# 16-PPSMUX_DPLLSMAMUX.net
KiCad netlist of a schematic drawn in Altium Designer
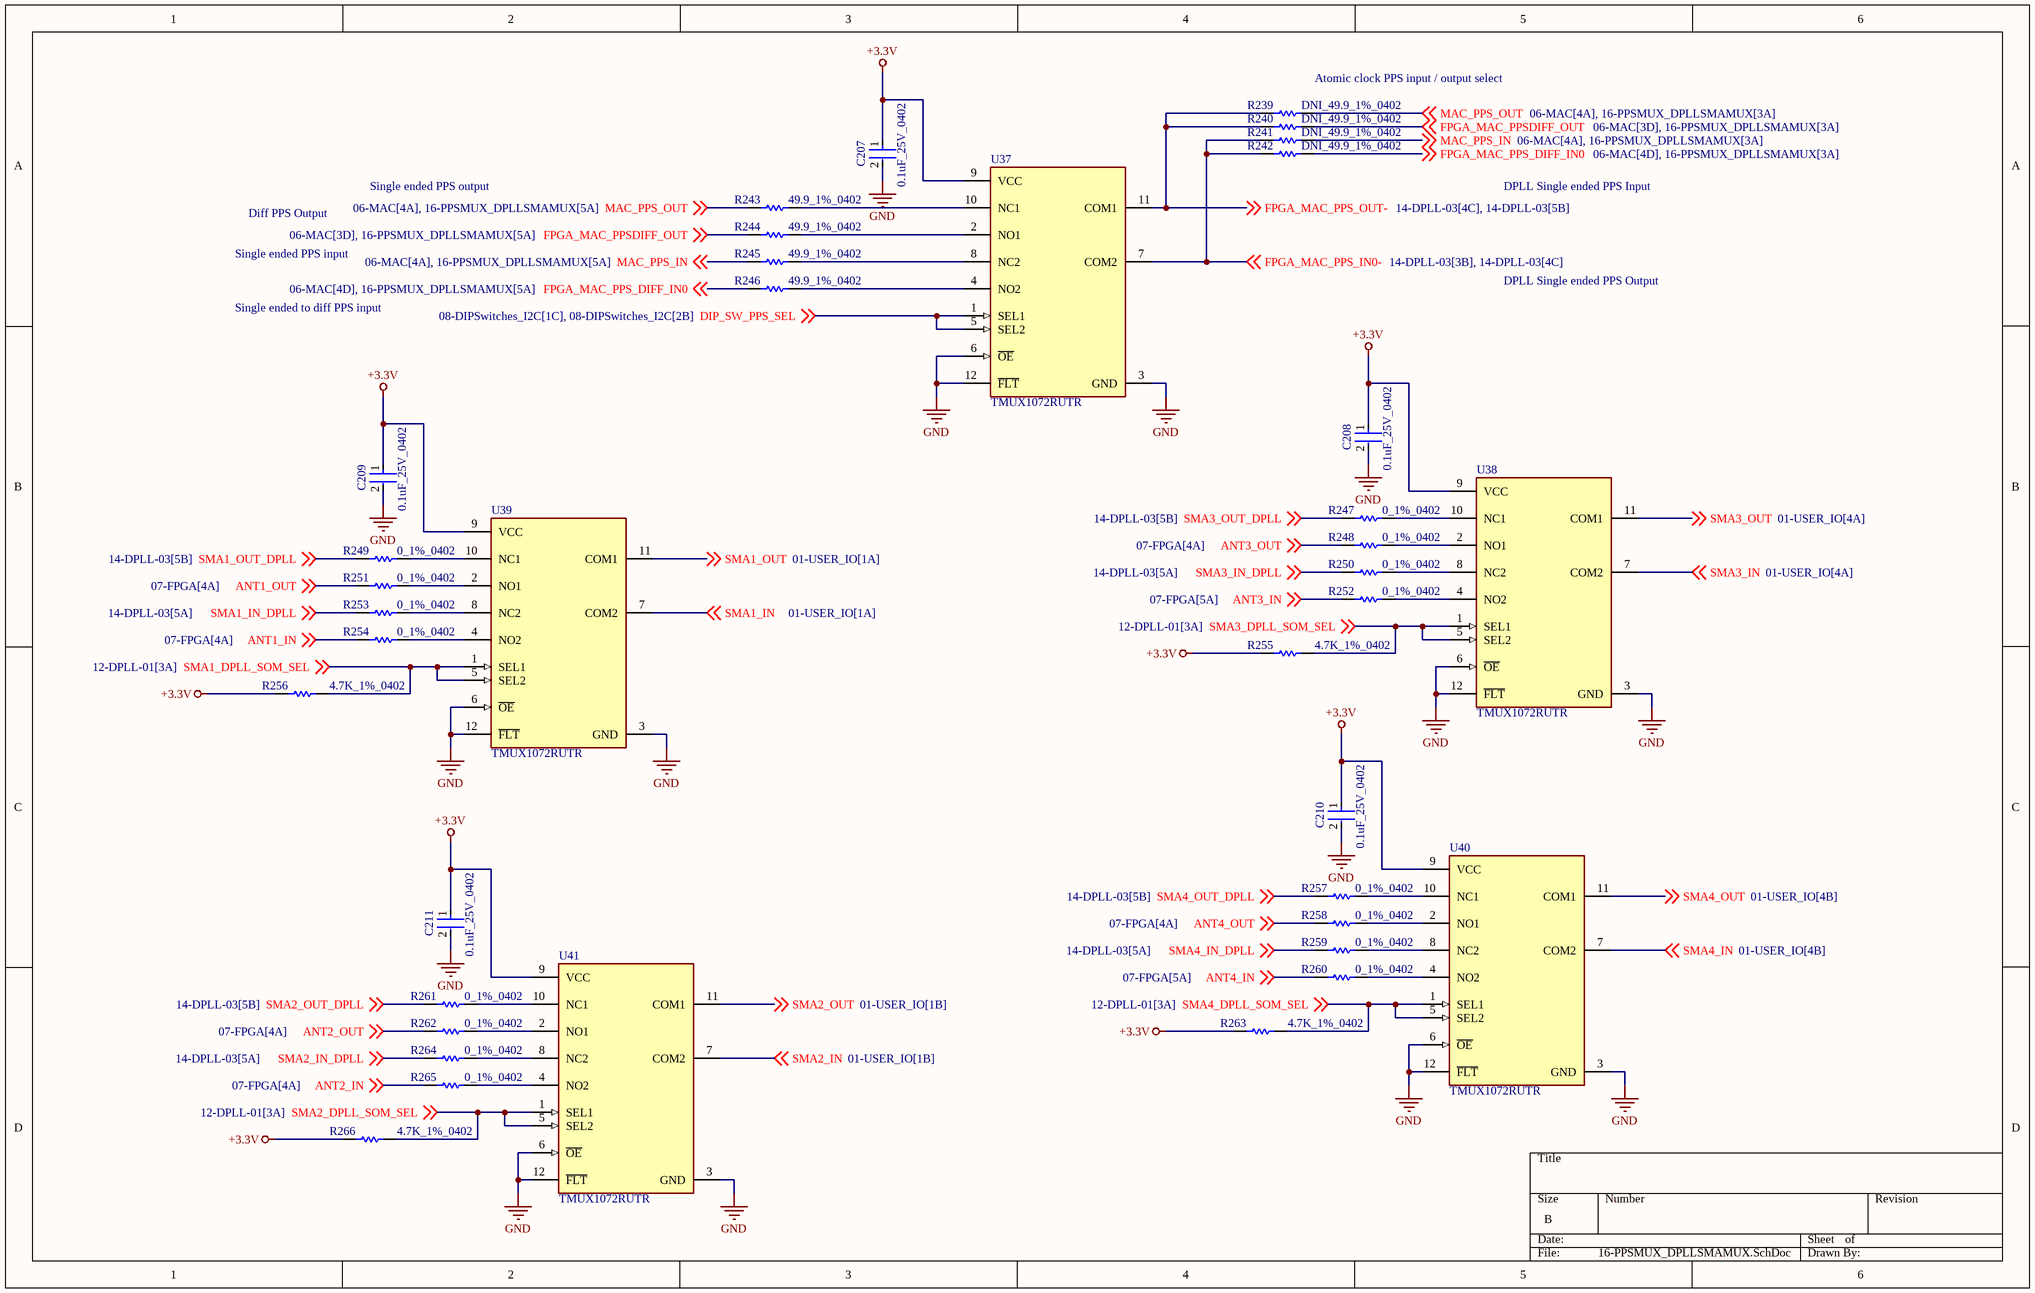
[diagram p0: 16-PPSMUX_DPLLSMAMUX.SchDoc]

(export (version "E")
  (design (tool "Eeschema 10.0.6"))
  (components
    (comp (ref "C207")
      (value "0.1uF_25V_0402")
      (footprint "FP-0402-L_1_0_1-W_0_5_0_1-IPC_C")
      (description "General Purpose Ceramic Capacitor, 0402, 100nF, 10%, X7R, 15%, 25V")
      (fields (field (name "VOLTAGE") "25V") (field (name "TOLERANCE") "10%"))
      (libsource (lib "Altium Content Vault") (part "b4654b650e69147ec39a6b967a45e02"))
    )
    (comp (ref "C208")
      (value "0.1uF_25V_0402")
      (footprint "FP-0402-L_1_0_1-W_0_5_0_1-IPC_C")
      (description "General Purpose Ceramic Capacitor, 0402, 100nF, 10%, X7R, 15%, 25V")
      (fields (field (name "VOLTAGE") "25V") (field (name "TOLERANCE") "10%"))
      (libsource (lib "Altium Content Vault") (part "b4654b650e69147ec39a6b967a45e02"))
    )
    (comp (ref "C209")
      (value "0.1uF_25V_0402")
      (footprint "FP-0402-L_1_0_1-W_0_5_0_1-IPC_C")
      (description "General Purpose Ceramic Capacitor, 0402, 100nF, 10%, X7R, 15%, 25V")
      (fields (field (name "VOLTAGE") "25V") (field (name "TOLERANCE") "10%"))
      (libsource (lib "Altium Content Vault") (part "b4654b650e69147ec39a6b967a45e02"))
    )
    (comp (ref "C210")
      (value "0.1uF_25V_0402")
      (footprint "FP-0402-L_1_0_1-W_0_5_0_1-IPC_C")
      (description "General Purpose Ceramic Capacitor, 0402, 100nF, 10%, X7R, 15%, 25V")
      (fields (field (name "VOLTAGE") "25V") (field (name "TOLERANCE") "10%"))
      (libsource (lib "Altium Content Vault") (part "b4654b650e69147ec39a6b967a45e02"))
    )
    (comp (ref "C211")
      (value "0.1uF_25V_0402")
      (footprint "FP-0402-L_1_0_1-W_0_5_0_1-IPC_C")
      (description "General Purpose Ceramic Capacitor, 0402, 100nF, 10%, X7R, 15%, 25V")
      (fields (field (name "VOLTAGE") "25V") (field (name "TOLERANCE") "10%"))
      (libsource (lib "Altium Content Vault") (part "b4654b650e69147ec39a6b967a45e02"))
    )
    (comp (ref "R239")
      (value "DNI_49.9_1%_0402")
      (footprint "RESC1005X40X25LL05T10")
      (fields (field (name "MANUFACTURER") "Yageo / Phycomp") (field (name "PART NUMBER") "RC0402FR-0749R9L"))
      (libsource (lib "Altium Content Vault") (part "RES"))
    )
    (comp (ref "R240")
      (value "DNI_49.9_1%_0402")
      (footprint "RESC1005X40X25LL05T10")
      (fields (field (name "MANUFACTURER") "Yageo / Phycomp") (field (name "PART NUMBER") "RC0402FR-0749R9L"))
      (libsource (lib "Altium Content Vault") (part "RES"))
    )
    (comp (ref "R241")
      (value "DNI_49.9_1%_0402")
      (footprint "RESC1005X40X25LL05T10")
      (fields (field (name "MANUFACTURER") "Yageo / Phycomp") (field (name "PART NUMBER") "RC0402FR-0749R9L"))
      (libsource (lib "Altium Content Vault") (part "RES"))
    )
    (comp (ref "R242")
      (value "DNI_49.9_1%_0402")
      (footprint "RESC1005X40X25LL05T10")
      (fields (field (name "MANUFACTURER") "Yageo / Phycomp") (field (name "PART NUMBER") "RC0402FR-0749R9L"))
      (libsource (lib "Altium Content Vault") (part "RES"))
    )
    (comp (ref "R243")
      (value "49.9_1%_0402")
      (footprint "RESC1005X40X25LL05T10")
      (fields (field (name "MANUFACTURER") "Yageo / Phycomp") (field (name "PART NUMBER") "RC0402FR-0749R9L"))
      (libsource (lib "Altium Content Vault") (part "RES"))
    )
    (comp (ref "R244")
      (value "49.9_1%_0402")
      (footprint "RESC1005X40X25LL05T10")
      (fields (field (name "MANUFACTURER") "Yageo / Phycomp") (field (name "PART NUMBER") "RC0402FR-0749R9L"))
      (libsource (lib "Altium Content Vault") (part "RES"))
    )
    (comp (ref "R245")
      (value "49.9_1%_0402")
      (footprint "RESC1005X40X25LL05T10")
      (fields (field (name "MANUFACTURER") "Yageo / Phycomp") (field (name "PART NUMBER") "RC0402FR-0749R9L"))
      (libsource (lib "Altium Content Vault") (part "RES"))
    )
    (comp (ref "R246")
      (value "49.9_1%_0402")
      (footprint "RESC1005X40X25LL05T10")
      (fields (field (name "MANUFACTURER") "Yageo / Phycomp") (field (name "PART NUMBER") "RC0402FR-0749R9L"))
      (libsource (lib "Altium Content Vault") (part "RES"))
    )
    (comp (ref "R247")
      (value "0_1%_0402")
      (footprint "RESC1005X40X25LL05T05")
      (description "Chip Resistor, 0 Ohm, 0.1 W, -55 to 155 degC, 0402 (1005 Metric), RoHS, Tape and Reel")
      (fields (field (name "MANUFACTURER") "Panasonic") (field (name "TOLERANCE") "5%"))
      (libsource (lib "Altium Content Vault") (part "RES-2"))
    )
    (comp (ref "R248")
      (value "0_1%_0402")
      (footprint "RESC1005X40X25LL05T05")
      (description "Chip Resistor, 0 Ohm, 0.1 W, -55 to 155 degC, 0402 (1005 Metric), RoHS, Tape and Reel")
      (fields (field (name "MANUFACTURER") "Panasonic") (field (name "TOLERANCE") "5%"))
      (libsource (lib "Altium Content Vault") (part "RES-2"))
    )
    (comp (ref "R249")
      (value "0_1%_0402")
      (footprint "RESC1005X40X25LL05T05")
      (description "Chip Resistor, 0 Ohm, 0.1 W, -55 to 155 degC, 0402 (1005 Metric), RoHS, Tape and Reel")
      (fields (field (name "MANUFACTURER") "Panasonic") (field (name "TOLERANCE") "5%"))
      (libsource (lib "Altium Content Vault") (part "RES-2"))
    )
    (comp (ref "R250")
      (value "0_1%_0402")
      (footprint "RESC1005X40X25LL05T05")
      (description "Chip Resistor, 0 Ohm, 0.1 W, -55 to 155 degC, 0402 (1005 Metric), RoHS, Tape and Reel")
      (fields (field (name "MANUFACTURER") "Panasonic") (field (name "TOLERANCE") "5%"))
      (libsource (lib "Altium Content Vault") (part "RES-2"))
    )
    (comp (ref "R251")
      (value "0_1%_0402")
      (footprint "RESC1005X40X25LL05T05")
      (description "Chip Resistor, 0 Ohm, 0.1 W, -55 to 155 degC, 0402 (1005 Metric), RoHS, Tape and Reel")
      (fields (field (name "MANUFACTURER") "Panasonic") (field (name "TOLERANCE") "5%"))
      (libsource (lib "Altium Content Vault") (part "RES-2"))
    )
    (comp (ref "R252")
      (value "0_1%_0402")
      (footprint "RESC1005X40X25LL05T05")
      (description "Chip Resistor, 0 Ohm, 0.1 W, -55 to 155 degC, 0402 (1005 Metric), RoHS, Tape and Reel")
      (fields (field (name "MANUFACTURER") "Panasonic") (field (name "TOLERANCE") "5%"))
      (libsource (lib "Altium Content Vault") (part "RES-2"))
    )
    (comp (ref "R253")
      (value "0_1%_0402")
      (footprint "RESC1005X40X25LL05T05")
      (description "Chip Resistor, 0 Ohm, 0.1 W, -55 to 155 degC, 0402 (1005 Metric), RoHS, Tape and Reel")
      (fields (field (name "MANUFACTURER") "Panasonic") (field (name "TOLERANCE") "5%"))
      (libsource (lib "Altium Content Vault") (part "RES-2"))
    )
    (comp (ref "R254")
      (value "0_1%_0402")
      (footprint "RESC1005X40X25LL05T05")
      (description "Chip Resistor, 0 Ohm, 0.1 W, -55 to 155 degC, 0402 (1005 Metric), RoHS, Tape and Reel")
      (fields (field (name "MANUFACTURER") "Panasonic") (field (name "TOLERANCE") "5%"))
      (libsource (lib "Altium Content Vault") (part "RES-2"))
    )
    (comp (ref "R255")
      (value "4.7K_1%_0402")
      (footprint "RESC1005X40X25NL10T10")
      (fields (field (name "MANUFACTURER") "Bourns") (field (name "PART NUMBER") "CR0402-FX-4701GLF"))
      (libsource (lib "Altium Content Vault") (part "RES"))
    )
    (comp (ref "R256")
      (value "4.7K_1%_0402")
      (footprint "RESC1005X40X25NL10T10")
      (fields (field (name "MANUFACTURER") "Bourns") (field (name "PART NUMBER") "CR0402-FX-4701GLF"))
      (libsource (lib "Altium Content Vault") (part "RES"))
    )
    (comp (ref "R257")
      (value "0_1%_0402")
      (footprint "RESC1005X40X25LL05T05")
      (description "Chip Resistor, 0 Ohm, 0.1 W, -55 to 155 degC, 0402 (1005 Metric), RoHS, Tape and Reel")
      (fields (field (name "MANUFACTURER") "Panasonic") (field (name "TOLERANCE") "5%"))
      (libsource (lib "Altium Content Vault") (part "RES-2"))
    )
    (comp (ref "R258")
      (value "0_1%_0402")
      (footprint "RESC1005X40X25LL05T05")
      (description "Chip Resistor, 0 Ohm, 0.1 W, -55 to 155 degC, 0402 (1005 Metric), RoHS, Tape and Reel")
      (fields (field (name "MANUFACTURER") "Panasonic") (field (name "TOLERANCE") "5%"))
      (libsource (lib "Altium Content Vault") (part "RES-2"))
    )
    (comp (ref "R259")
      (value "0_1%_0402")
      (footprint "RESC1005X40X25LL05T05")
      (description "Chip Resistor, 0 Ohm, 0.1 W, -55 to 155 degC, 0402 (1005 Metric), RoHS, Tape and Reel")
      (fields (field (name "MANUFACTURER") "Panasonic") (field (name "TOLERANCE") "5%"))
      (libsource (lib "Altium Content Vault") (part "RES-2"))
    )
    (comp (ref "R260")
      (value "0_1%_0402")
      (footprint "RESC1005X40X25LL05T05")
      (description "Chip Resistor, 0 Ohm, 0.1 W, -55 to 155 degC, 0402 (1005 Metric), RoHS, Tape and Reel")
      (fields (field (name "MANUFACTURER") "Panasonic") (field (name "TOLERANCE") "5%"))
      (libsource (lib "Altium Content Vault") (part "RES-2"))
    )
    (comp (ref "R261")
      (value "0_1%_0402")
      (footprint "RESC1005X40X25LL05T05")
      (description "Chip Resistor, 0 Ohm, 0.1 W, -55 to 155 degC, 0402 (1005 Metric), RoHS, Tape and Reel")
      (fields (field (name "MANUFACTURER") "Panasonic") (field (name "TOLERANCE") "5%"))
      (libsource (lib "Altium Content Vault") (part "RES-2"))
    )
    (comp (ref "R262")
      (value "0_1%_0402")
      (footprint "RESC1005X40X25LL05T05")
      (description "Chip Resistor, 0 Ohm, 0.1 W, -55 to 155 degC, 0402 (1005 Metric), RoHS, Tape and Reel")
      (fields (field (name "MANUFACTURER") "Panasonic") (field (name "TOLERANCE") "5%"))
      (libsource (lib "Altium Content Vault") (part "RES-2"))
    )
    (comp (ref "R263")
      (value "4.7K_1%_0402")
      (footprint "RESC1005X40X25NL10T10")
      (fields (field (name "MANUFACTURER") "Bourns") (field (name "PART NUMBER") "CR0402-FX-4701GLF"))
      (libsource (lib "Altium Content Vault") (part "RES"))
    )
    (comp (ref "R264")
      (value "0_1%_0402")
      (footprint "RESC1005X40X25LL05T05")
      (description "Chip Resistor, 0 Ohm, 0.1 W, -55 to 155 degC, 0402 (1005 Metric), RoHS, Tape and Reel")
      (fields (field (name "MANUFACTURER") "Panasonic") (field (name "TOLERANCE") "5%"))
      (libsource (lib "Altium Content Vault") (part "RES-2"))
    )
    (comp (ref "R265")
      (value "0_1%_0402")
      (footprint "RESC1005X40X25LL05T05")
      (description "Chip Resistor, 0 Ohm, 0.1 W, -55 to 155 degC, 0402 (1005 Metric), RoHS, Tape and Reel")
      (fields (field (name "MANUFACTURER") "Panasonic") (field (name "TOLERANCE") "5%"))
      (libsource (lib "Altium Content Vault") (part "RES-2"))
    )
    (comp (ref "R266")
      (value "4.7K_1%_0402")
      (footprint "RESC1005X40X25NL10T10")
      (fields (field (name "MANUFACTURER") "Bourns") (field (name "PART NUMBER") "CR0402-FX-4701GLF"))
      (libsource (lib "Altium Content Vault") (part "RES"))
    )
    (comp (ref "U37")
      (value "TMUX1072RUTR")
      (footprint "FP-RUT0012A-MFG")
      (description "IC SWITCH SPDT DUAL 12UQFN")
      (libsource (lib "Altium Content Vault") (part "12a319ab100cd6cfe745e35972674f5"))
    )
    (comp (ref "U38")
      (value "TMUX1072RUTR")
      (footprint "FP-RUT0012A-MFG")
      (description "IC SWITCH SPDT DUAL 12UQFN")
      (libsource (lib "Altium Content Vault") (part "12a319ab100cd6cfe745e35972674f5"))
    )
    (comp (ref "U39")
      (value "TMUX1072RUTR")
      (footprint "FP-RUT0012A-MFG")
      (description "IC SWITCH SPDT DUAL 12UQFN")
      (libsource (lib "Altium Content Vault") (part "12a319ab100cd6cfe745e35972674f5"))
    )
    (comp (ref "U40")
      (value "TMUX1072RUTR")
      (footprint "FP-RUT0012A-MFG")
      (description "IC SWITCH SPDT DUAL 12UQFN")
      (libsource (lib "Altium Content Vault") (part "12a319ab100cd6cfe745e35972674f5"))
    )
    (comp (ref "U41")
      (value "TMUX1072RUTR")
      (footprint "FP-RUT0012A-MFG")
      (description "IC SWITCH SPDT DUAL 12UQFN")
      (libsource (lib "Altium Content Vault") (part "12a319ab100cd6cfe745e35972674f5"))
    )
  )
  (nets
    (net (code "1") (name "+3.3V") (class "Default")
      (node (ref "C207") (pin "1") (pinfunction "1_1") (pintype "passive"))
      (node (ref "C208") (pin "1") (pinfunction "1_1") (pintype "passive"))
      (node (ref "C209") (pin "1") (pinfunction "1_1") (pintype "passive"))
      (node (ref "C210") (pin "1") (pinfunction "1_1") (pintype "passive"))
      (node (ref "C211") (pin "1") (pinfunction "1_1") (pintype "passive"))
      (node (ref "R255") (pin "2") (pinfunction "2_2") (pintype "passive"))
      (node (ref "R256") (pin "2") (pinfunction "2_2") (pintype "passive"))
      (node (ref "R263") (pin "2") (pinfunction "2_2") (pintype "passive"))
      (node (ref "R266") (pin "2") (pinfunction "2_2") (pintype "passive"))
      (node (ref "U37") (pin "9") (pinfunction "VCC_9") (pintype "power_in"))
      (node (ref "U38") (pin "9") (pinfunction "VCC_9") (pintype "power_in"))
      (node (ref "U39") (pin "9") (pinfunction "VCC_9") (pintype "power_in"))
      (node (ref "U40") (pin "9") (pinfunction "VCC_9") (pintype "power_in"))
      (node (ref "U41") (pin "9") (pinfunction "VCC_9") (pintype "power_in"))
    )
    (net (code "2") (name "ANT1_IN") (class "Default")
      (node (ref "R254") (pin "1") (pinfunction "1_1") (pintype "passive"))
    )
    (net (code "3") (name "ANT1_OUT") (class "Default")
      (node (ref "R251") (pin "1") (pinfunction "1_1") (pintype "passive"))
    )
    (net (code "4") (name "ANT2_IN") (class "Default")
      (node (ref "R265") (pin "1") (pinfunction "1_1") (pintype "passive"))
    )
    (net (code "5") (name "ANT2_OUT") (class "Default")
      (node (ref "R262") (pin "1") (pinfunction "1_1") (pintype "passive"))
    )
    (net (code "6") (name "ANT3_IN") (class "Default")
      (node (ref "R252") (pin "1") (pinfunction "1_1") (pintype "passive"))
    )
    (net (code "7") (name "ANT3_OUT") (class "Default")
      (node (ref "R248") (pin "1") (pinfunction "1_1") (pintype "passive"))
    )
    (net (code "8") (name "ANT4_IN") (class "Default")
      (node (ref "R260") (pin "1") (pinfunction "1_1") (pintype "passive"))
    )
    (net (code "9") (name "ANT4_OUT") (class "Default")
      (node (ref "R258") (pin "1") (pinfunction "1_1") (pintype "passive"))
    )
    (net (code "10") (name "DIP_SW_PPS_SEL") (class "Default")
      (node (ref "U37") (pin "1") (pinfunction "SEL1_1") (pintype "input"))
      (node (ref "U37") (pin "5") (pinfunction "SEL2_5") (pintype "input"))
    )
    (net (code "11") (name "FPGA_MAC_PPSDIFF_OUT") (class "Default")
      (node (ref "R240") (pin "2") (pinfunction "2_2") (pintype "passive"))
      (node (ref "R244") (pin "1") (pinfunction "1_1") (pintype "passive"))
    )
    (net (code "12") (name "FPGA_MAC_PPS_DIFF_IN0") (class "Default")
      (node (ref "R242") (pin "2") (pinfunction "2_2") (pintype "passive"))
      (node (ref "R246") (pin "1") (pinfunction "1_1") (pintype "passive"))
    )
    (net (code "13") (name "FPGA_MAC_PPS_IN0-") (class "Default")
      (node (ref "R241") (pin "1") (pinfunction "1_1") (pintype "passive"))
      (node (ref "R242") (pin "1") (pinfunction "1_1") (pintype "passive"))
      (node (ref "U37") (pin "7") (pinfunction "COM2_7") (pintype "passive"))
    )
    (net (code "14") (name "FPGA_MAC_PPS_OUT-") (class "Default")
      (node (ref "R239") (pin "1") (pinfunction "1_1") (pintype "passive"))
      (node (ref "R240") (pin "1") (pinfunction "1_1") (pintype "passive"))
      (node (ref "U37") (pin "11") (pinfunction "COM1_11") (pintype "passive"))
    )
    (net (code "15") (name "GND") (class "Default")
      (node (ref "C207") (pin "2") (pinfunction "2_2") (pintype "passive"))
      (node (ref "C208") (pin "2") (pinfunction "2_2") (pintype "passive"))
      (node (ref "C209") (pin "2") (pinfunction "2_2") (pintype "passive"))
      (node (ref "C210") (pin "2") (pinfunction "2_2") (pintype "passive"))
      (node (ref "C211") (pin "2") (pinfunction "2_2") (pintype "passive"))
      (node (ref "U37") (pin "12") (pinfunction "~{FLT}_12") (pintype "open_collector"))
      (node (ref "U37") (pin "3") (pinfunction "GND_3") (pintype "power_in"))
      (node (ref "U37") (pin "6") (pinfunction "~{OE}_6") (pintype "input"))
      (node (ref "U38") (pin "12") (pinfunction "~{FLT}_12") (pintype "open_collector"))
      (node (ref "U38") (pin "3") (pinfunction "GND_3") (pintype "power_in"))
      (node (ref "U38") (pin "6") (pinfunction "~{OE}_6") (pintype "input"))
      (node (ref "U39") (pin "12") (pinfunction "~{FLT}_12") (pintype "open_collector"))
      (node (ref "U39") (pin "3") (pinfunction "GND_3") (pintype "power_in"))
      (node (ref "U39") (pin "6") (pinfunction "~{OE}_6") (pintype "input"))
      (node (ref "U40") (pin "12") (pinfunction "~{FLT}_12") (pintype "open_collector"))
      (node (ref "U40") (pin "3") (pinfunction "GND_3") (pintype "power_in"))
      (node (ref "U40") (pin "6") (pinfunction "~{OE}_6") (pintype "input"))
      (node (ref "U41") (pin "12") (pinfunction "~{FLT}_12") (pintype "open_collector"))
      (node (ref "U41") (pin "3") (pinfunction "GND_3") (pintype "power_in"))
      (node (ref "U41") (pin "6") (pinfunction "~{OE}_6") (pintype "input"))
    )
    (net (code "16") (name "MAC_PPS_IN") (class "Default")
      (node (ref "R241") (pin "2") (pinfunction "2_2") (pintype "passive"))
      (node (ref "R245") (pin "1") (pinfunction "1_1") (pintype "passive"))
    )
    (net (code "17") (name "MAC_PPS_OUT") (class "Default")
      (node (ref "R239") (pin "2") (pinfunction "2_2") (pintype "passive"))
      (node (ref "R243") (pin "1") (pinfunction "1_1") (pintype "passive"))
    )
    (net (code "18") (name "Net-(U37-NC1)") (class "Default")
      (node (ref "R243") (pin "2") (pinfunction "2_2") (pintype "passive"))
      (node (ref "U37") (pin "10") (pinfunction "NC1_10") (pintype "passive"))
    )
    (net (code "19") (name "Net-(U37-NC2)") (class "Default")
      (node (ref "R245") (pin "2") (pinfunction "2_2") (pintype "passive"))
      (node (ref "U37") (pin "8") (pinfunction "NC2_8") (pintype "passive"))
    )
    (net (code "20") (name "Net-(U37-NO1)") (class "Default")
      (node (ref "R244") (pin "2") (pinfunction "2_2") (pintype "passive"))
      (node (ref "U37") (pin "2") (pinfunction "NO1_2") (pintype "passive"))
    )
    (net (code "21") (name "Net-(U37-NO2)") (class "Default")
      (node (ref "R246") (pin "2") (pinfunction "2_2") (pintype "passive"))
      (node (ref "U37") (pin "4") (pinfunction "NO2_4") (pintype "passive"))
    )
    (net (code "22") (name "Net-(U38-NC1)") (class "Default")
      (node (ref "R247") (pin "2") (pinfunction "2_2") (pintype "passive"))
      (node (ref "U38") (pin "10") (pinfunction "NC1_10") (pintype "passive"))
    )
    (net (code "23") (name "Net-(U38-NC2)") (class "Default")
      (node (ref "R250") (pin "2") (pinfunction "2_2") (pintype "passive"))
      (node (ref "U38") (pin "8") (pinfunction "NC2_8") (pintype "passive"))
    )
    (net (code "24") (name "Net-(U38-NO1)") (class "Default")
      (node (ref "R248") (pin "2") (pinfunction "2_2") (pintype "passive"))
      (node (ref "U38") (pin "2") (pinfunction "NO1_2") (pintype "passive"))
    )
    (net (code "25") (name "Net-(U38-NO2)") (class "Default")
      (node (ref "R252") (pin "2") (pinfunction "2_2") (pintype "passive"))
      (node (ref "U38") (pin "4") (pinfunction "NO2_4") (pintype "passive"))
    )
    (net (code "26") (name "Net-(U39-NC1)") (class "Default")
      (node (ref "R249") (pin "2") (pinfunction "2_2") (pintype "passive"))
      (node (ref "U39") (pin "10") (pinfunction "NC1_10") (pintype "passive"))
    )
    (net (code "27") (name "Net-(U39-NC2)") (class "Default")
      (node (ref "R253") (pin "2") (pinfunction "2_2") (pintype "passive"))
      (node (ref "U39") (pin "8") (pinfunction "NC2_8") (pintype "passive"))
    )
    (net (code "28") (name "Net-(U39-NO1)") (class "Default")
      (node (ref "R251") (pin "2") (pinfunction "2_2") (pintype "passive"))
      (node (ref "U39") (pin "2") (pinfunction "NO1_2") (pintype "passive"))
    )
    (net (code "29") (name "Net-(U39-NO2)") (class "Default")
      (node (ref "R254") (pin "2") (pinfunction "2_2") (pintype "passive"))
      (node (ref "U39") (pin "4") (pinfunction "NO2_4") (pintype "passive"))
    )
    (net (code "30") (name "Net-(U40-NC1)") (class "Default")
      (node (ref "R257") (pin "2") (pinfunction "2_2") (pintype "passive"))
      (node (ref "U40") (pin "10") (pinfunction "NC1_10") (pintype "passive"))
    )
    (net (code "31") (name "Net-(U40-NC2)") (class "Default")
      (node (ref "R259") (pin "2") (pinfunction "2_2") (pintype "passive"))
      (node (ref "U40") (pin "8") (pinfunction "NC2_8") (pintype "passive"))
    )
    (net (code "32") (name "Net-(U40-NO1)") (class "Default")
      (node (ref "R258") (pin "2") (pinfunction "2_2") (pintype "passive"))
      (node (ref "U40") (pin "2") (pinfunction "NO1_2") (pintype "passive"))
    )
    (net (code "33") (name "Net-(U40-NO2)") (class "Default")
      (node (ref "R260") (pin "2") (pinfunction "2_2") (pintype "passive"))
      (node (ref "U40") (pin "4") (pinfunction "NO2_4") (pintype "passive"))
    )
    (net (code "34") (name "Net-(U41-NC1)") (class "Default")
      (node (ref "R261") (pin "2") (pinfunction "2_2") (pintype "passive"))
      (node (ref "U41") (pin "10") (pinfunction "NC1_10") (pintype "passive"))
    )
    (net (code "35") (name "Net-(U41-NC2)") (class "Default")
      (node (ref "R264") (pin "2") (pinfunction "2_2") (pintype "passive"))
      (node (ref "U41") (pin "8") (pinfunction "NC2_8") (pintype "passive"))
    )
    (net (code "36") (name "Net-(U41-NO1)") (class "Default")
      (node (ref "R262") (pin "2") (pinfunction "2_2") (pintype "passive"))
      (node (ref "U41") (pin "2") (pinfunction "NO1_2") (pintype "passive"))
    )
    (net (code "37") (name "Net-(U41-NO2)") (class "Default")
      (node (ref "R265") (pin "2") (pinfunction "2_2") (pintype "passive"))
      (node (ref "U41") (pin "4") (pinfunction "NO2_4") (pintype "passive"))
    )
    (net (code "38") (name "SMA1_DPLL_SOM_SEL") (class "Default")
      (node (ref "R256") (pin "1") (pinfunction "1_1") (pintype "passive"))
      (node (ref "U39") (pin "1") (pinfunction "SEL1_1") (pintype "input"))
      (node (ref "U39") (pin "5") (pinfunction "SEL2_5") (pintype "input"))
    )
    (net (code "39") (name "SMA1_IN") (class "Default")
      (node (ref "U39") (pin "7") (pinfunction "COM2_7") (pintype "passive"))
    )
    (net (code "40") (name "SMA1_IN_DPLL") (class "Default")
      (node (ref "R253") (pin "1") (pinfunction "1_1") (pintype "passive"))
    )
    (net (code "41") (name "SMA1_OUT") (class "Default")
      (node (ref "U39") (pin "11") (pinfunction "COM1_11") (pintype "passive"))
    )
    (net (code "42") (name "SMA1_OUT_DPLL") (class "Default")
      (node (ref "R249") (pin "1") (pinfunction "1_1") (pintype "passive"))
    )
    (net (code "43") (name "SMA2_DPLL_SOM_SEL") (class "Default")
      (node (ref "R266") (pin "1") (pinfunction "1_1") (pintype "passive"))
      (node (ref "U41") (pin "1") (pinfunction "SEL1_1") (pintype "input"))
      (node (ref "U41") (pin "5") (pinfunction "SEL2_5") (pintype "input"))
    )
    (net (code "44") (name "SMA2_IN") (class "Default")
      (node (ref "U41") (pin "7") (pinfunction "COM2_7") (pintype "passive"))
    )
    (net (code "45") (name "SMA2_IN_DPLL") (class "Default")
      (node (ref "R264") (pin "1") (pinfunction "1_1") (pintype "passive"))
    )
    (net (code "46") (name "SMA2_OUT") (class "Default")
      (node (ref "U41") (pin "11") (pinfunction "COM1_11") (pintype "passive"))
    )
    (net (code "47") (name "SMA2_OUT_DPLL") (class "Default")
      (node (ref "R261") (pin "1") (pinfunction "1_1") (pintype "passive"))
    )
    (net (code "48") (name "SMA3_DPLL_SOM_SEL") (class "Default")
      (node (ref "R255") (pin "1") (pinfunction "1_1") (pintype "passive"))
      (node (ref "U38") (pin "1") (pinfunction "SEL1_1") (pintype "input"))
      (node (ref "U38") (pin "5") (pinfunction "SEL2_5") (pintype "input"))
    )
    (net (code "49") (name "SMA3_IN") (class "Default")
      (node (ref "U38") (pin "7") (pinfunction "COM2_7") (pintype "passive"))
    )
    (net (code "50") (name "SMA3_IN_DPLL") (class "Default")
      (node (ref "R250") (pin "1") (pinfunction "1_1") (pintype "passive"))
    )
    (net (code "51") (name "SMA3_OUT") (class "Default")
      (node (ref "U38") (pin "11") (pinfunction "COM1_11") (pintype "passive"))
    )
    (net (code "52") (name "SMA3_OUT_DPLL") (class "Default")
      (node (ref "R247") (pin "1") (pinfunction "1_1") (pintype "passive"))
    )
    (net (code "53") (name "SMA4_DPLL_SOM_SEL") (class "Default")
      (node (ref "R263") (pin "1") (pinfunction "1_1") (pintype "passive"))
      (node (ref "U40") (pin "1") (pinfunction "SEL1_1") (pintype "input"))
      (node (ref "U40") (pin "5") (pinfunction "SEL2_5") (pintype "input"))
    )
    (net (code "54") (name "SMA4_IN") (class "Default")
      (node (ref "U40") (pin "7") (pinfunction "COM2_7") (pintype "passive"))
    )
    (net (code "55") (name "SMA4_IN_DPLL") (class "Default")
      (node (ref "R259") (pin "1") (pinfunction "1_1") (pintype "passive"))
    )
    (net (code "56") (name "SMA4_OUT") (class "Default")
      (node (ref "U40") (pin "11") (pinfunction "COM1_11") (pintype "passive"))
    )
    (net (code "57") (name "SMA4_OUT_DPLL") (class "Default")
      (node (ref "R257") (pin "1") (pinfunction "1_1") (pintype "passive"))
    )
  )
)
